# staff-pdb-a.net
KiCad netlist of a schematic drawn in EAGLE
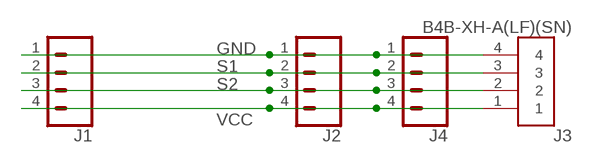
[diagram p0: schematic, sheet 1]

(export (version "E")
  (design (tool "Eeschema 10.0.6"))
  (components
    (comp (ref "J1")
      (value "CONN_04")
      (footprint "eagle-import:1X04")
      (libsource (lib "eagle-import") (part "CONN_04"))
    )
    (comp (ref "J2")
      (value "CONN_04")
      (footprint "eagle-import:1X04")
      (libsource (lib "eagle-import") (part "CONN_04"))
    )
    (comp (ref "J3")
      (value "B4B-XH-A(LF)(SN)")
      (footprint "eagle-import:JST_B4B-XH-A(LF)(SN)")
      (fields (field (name "DIGI-KEY_PART_NUMBER") "455-2249-ND") (field (name "MF") "JST Sales"))
      (libsource (lib "eagle-import") (part "B4B-XH-A(LF)(SN)"))
    )
    (comp (ref "J4")
      (value "CONN_04")
      (footprint "eagle-import:1X04")
      (libsource (lib "eagle-import") (part "CONN_04"))
    )
  )
  (nets
    (net (code "1") (name "/GND") (class "Default")
      (node (ref "J1") (pin "1") (pinfunction "1_1") (pintype "passive"))
      (node (ref "J2") (pin "1") (pinfunction "1_1") (pintype "passive"))
      (node (ref "J3") (pin "4") (pinfunction "4_4") (pintype "passive"))
      (node (ref "J4") (pin "1") (pinfunction "1_1") (pintype "passive"))
    )
    (net (code "2") (name "/S1") (class "Default")
      (node (ref "J1") (pin "2") (pinfunction "2_2") (pintype "passive"))
      (node (ref "J2") (pin "2") (pinfunction "2_2") (pintype "passive"))
      (node (ref "J3") (pin "3") (pinfunction "3_3") (pintype "passive"))
      (node (ref "J4") (pin "2") (pinfunction "2_2") (pintype "passive"))
    )
    (net (code "3") (name "/S2") (class "Default")
      (node (ref "J1") (pin "3") (pinfunction "3_3") (pintype "passive"))
      (node (ref "J2") (pin "3") (pinfunction "3_3") (pintype "passive"))
      (node (ref "J3") (pin "2") (pinfunction "2_2") (pintype "passive"))
      (node (ref "J4") (pin "3") (pinfunction "3_3") (pintype "passive"))
    )
    (net (code "4") (name "/VCC") (class "Default")
      (node (ref "J1") (pin "4") (pinfunction "4_4") (pintype "passive"))
      (node (ref "J2") (pin "4") (pinfunction "4_4") (pintype "passive"))
      (node (ref "J3") (pin "1") (pinfunction "1_1") (pintype "passive"))
      (node (ref "J4") (pin "4") (pinfunction "4_4") (pintype "passive"))
    )
  )
)
